# Sheet1.net
KiCad netlist of a schematic drawn in Altium Designer
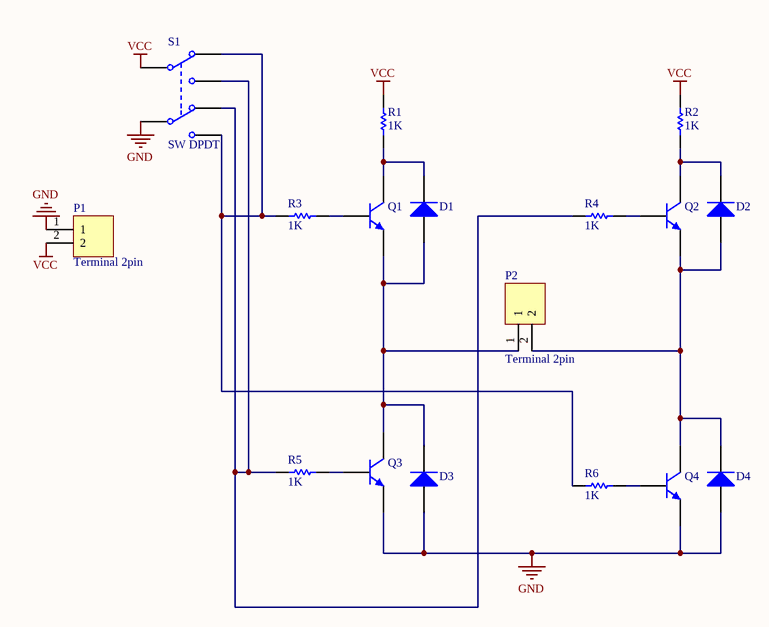
[diagram p0: Sheet1.SchDoc]

(export (version "E")
  (design (tool "Eeschema 10.0.6"))
  (components
    (comp (ref "D1")
      (value "1N4007")
      (footprint "DO-41")
      (description "1 Amp Diode")
      (libsource (lib "My_LIB") (part "1N4007"))
    )
    (comp (ref "D2")
      (value "1N4007")
      (footprint "DO-41")
      (description "1 Amp Diode")
      (libsource (lib "My_LIB") (part "1N4007"))
    )
    (comp (ref "D3")
      (value "1N4007")
      (footprint "DO-41")
      (description "1 Amp Diode")
      (libsource (lib "My_LIB") (part "1N4007"))
    )
    (comp (ref "D4")
      (value "1N4007")
      (footprint "DO-41")
      (description "1 Amp Diode")
      (libsource (lib "My_LIB") (part "1N4007"))
    )
    (comp (ref "P1")
      (value "Terminal 2pin")
      (footprint "Terminal 2pin")
      (libsource (lib "") (part "Terminal 2pin_1"))
    )
    (comp (ref "P2")
      (value "Terminal 2pin")
      (footprint "Terminal 2pin")
      (libsource (lib "My_LIB") (part "Terminal 2pin"))
    )
    (comp (ref "Q1")
      (value "2N2222A")
      (footprint "TO-18")
      (description "High Speed Switches")
      (fields (field (name "PUBLISHER") "Altium Limited"))
      (libsource (lib "ST Discrete BJT") (part "2N2222A"))
    )
    (comp (ref "Q2")
      (value "2N2222A")
      (footprint "TO-18")
      (description "High Speed Switches")
      (fields (field (name "PUBLISHER") "Altium Limited"))
      (libsource (lib "ST Discrete BJT") (part "2N2222A"))
    )
    (comp (ref "Q3")
      (value "2N2222A")
      (footprint "TO-18")
      (description "High Speed Switches")
      (fields (field (name "PUBLISHER") "Altium Limited"))
      (libsource (lib "ST Discrete BJT") (part "2N2222A"))
    )
    (comp (ref "Q4")
      (value "2N2222A")
      (footprint "TO-18")
      (description "High Speed Switches")
      (fields (field (name "PUBLISHER") "Altium Limited"))
      (libsource (lib "ST Discrete BJT") (part "2N2222A"))
    )
    (comp (ref "R1") (value "1K") (footprint "Axial-0.4-0.25W") (libsource (lib "My_LIB") (part "RES")))
    (comp (ref "R2") (value "1K") (footprint "Axial-0.4-0.25W") (libsource (lib "My_LIB") (part "RES")))
    (comp (ref "R3") (value "1K") (footprint "Axial-0.4-0.25W") (libsource (lib "My_LIB") (part "RES")))
    (comp (ref "R4") (value "1K") (footprint "Axial-0.4-0.25W") (libsource (lib "My_LIB") (part "RES")))
    (comp (ref "R5") (value "1K") (footprint "Axial-0.4-0.25W") (libsource (lib "My_LIB") (part "RES")))
    (comp (ref "R6") (value "1K") (footprint "Axial-0.4-0.25W") (libsource (lib "My_LIB") (part "RES")))
    (comp (ref "S1")
      (value "SW DPDT")
      (footprint "SOT23-6_N")
      (description "Switch")
      (fields (field (name "PUBLISHER") "Altium Limited"))
      (libsource (lib "Miscellaneous Devices") (part "SW DPDT"))
    )
  )
  (nets
    (net (code "1") (name "GND") (class "Default")
      (node (ref "D3") (pin "1") (pinfunction "A_1") (pintype "passive"))
      (node (ref "D4") (pin "1") (pinfunction "A_1") (pintype "passive"))
      (node (ref "P1") (pin "1") (pinfunction "1_1") (pintype "passive"))
      (node (ref "Q3") (pin "3") (pinfunction "E_3") (pintype "passive"))
      (node (ref "Q4") (pin "3") (pinfunction "E_3") (pintype "passive"))
      (node (ref "S1") (pin "5") (pinfunction "COMMON2_5") (pintype "passive"))
    )
    (net (code "2") (name "Net-(D1-A)") (class "Default")
      (node (ref "D1") (pin "1") (pinfunction "A_1") (pintype "passive"))
      (node (ref "D3") (pin "2") (pinfunction "K_2") (pintype "passive"))
      (node (ref "P2") (pin "1") (pinfunction "1_1") (pintype "passive"))
      (node (ref "Q1") (pin "3") (pinfunction "E_3") (pintype "passive"))
      (node (ref "Q3") (pin "2") (pinfunction "C_2") (pintype "passive"))
    )
    (net (code "3") (name "Net-(D1-K)") (class "Default")
      (node (ref "D1") (pin "2") (pinfunction "K_2") (pintype "passive"))
      (node (ref "Q1") (pin "2") (pinfunction "C_2") (pintype "passive"))
      (node (ref "R1") (pin "1") (pinfunction "1_1") (pintype "passive"))
    )
    (net (code "4") (name "Net-(D2-A)") (class "Default")
      (node (ref "D2") (pin "1") (pinfunction "A_1") (pintype "passive"))
      (node (ref "D4") (pin "2") (pinfunction "K_2") (pintype "passive"))
      (node (ref "P2") (pin "2") (pinfunction "2_2") (pintype "passive"))
      (node (ref "Q2") (pin "3") (pinfunction "E_3") (pintype "passive"))
      (node (ref "Q4") (pin "2") (pinfunction "C_2") (pintype "passive"))
    )
    (net (code "5") (name "Net-(D2-K)") (class "Default")
      (node (ref "D2") (pin "2") (pinfunction "K_2") (pintype "passive"))
      (node (ref "Q2") (pin "2") (pinfunction "C_2") (pintype "passive"))
      (node (ref "R2") (pin "1") (pinfunction "1_1") (pintype "passive"))
    )
    (net (code "6") (name "Net-(Q1-B)") (class "Default")
      (node (ref "Q1") (pin "1") (pinfunction "B_1") (pintype "passive"))
      (node (ref "R3") (pin "1") (pinfunction "1_1") (pintype "passive"))
    )
    (net (code "7") (name "Net-(Q2-B)") (class "Default")
      (node (ref "Q2") (pin "1") (pinfunction "B_1") (pintype "passive"))
      (node (ref "R4") (pin "1") (pinfunction "1_1") (pintype "passive"))
    )
    (net (code "8") (name "Net-(Q3-B)") (class "Default")
      (node (ref "Q3") (pin "1") (pinfunction "B_1") (pintype "passive"))
      (node (ref "R5") (pin "1") (pinfunction "1_1") (pintype "passive"))
    )
    (net (code "9") (name "Net-(Q4-B)") (class "Default")
      (node (ref "Q4") (pin "1") (pinfunction "B_1") (pintype "passive"))
      (node (ref "R6") (pin "1") (pinfunction "1_1") (pintype "passive"))
    )
    (net (code "10") (name "Net-(S1-NC1)") (class "Default")
      (node (ref "R3") (pin "2") (pinfunction "2_2") (pintype "passive"))
      (node (ref "R6") (pin "2") (pinfunction "2_2") (pintype "passive"))
      (node (ref "S1") (pin "2") (pinfunction "NC1_2") (pintype "passive"))
      (node (ref "S1") (pin "6") (pinfunction "NO2_6") (pintype "passive"))
    )
    (net (code "11") (name "Net-(S1-NC2)") (class "Default")
      (node (ref "R4") (pin "2") (pinfunction "2_2") (pintype "passive"))
      (node (ref "R5") (pin "2") (pinfunction "2_2") (pintype "passive"))
      (node (ref "S1") (pin "3") (pinfunction "NO1_3") (pintype "passive"))
      (node (ref "S1") (pin "4") (pinfunction "NC2_4") (pintype "passive"))
    )
    (net (code "12") (name "VCC") (class "Default")
      (node (ref "P1") (pin "2") (pinfunction "2_2") (pintype "passive"))
      (node (ref "R1") (pin "2") (pinfunction "2_2") (pintype "passive"))
      (node (ref "R2") (pin "2") (pinfunction "2_2") (pintype "passive"))
      (node (ref "S1") (pin "1") (pinfunction "COMMON1_1") (pintype "passive"))
    )
  )
)
